# ATtiny85.net
KiCad netlist of a schematic drawn in EAGLE
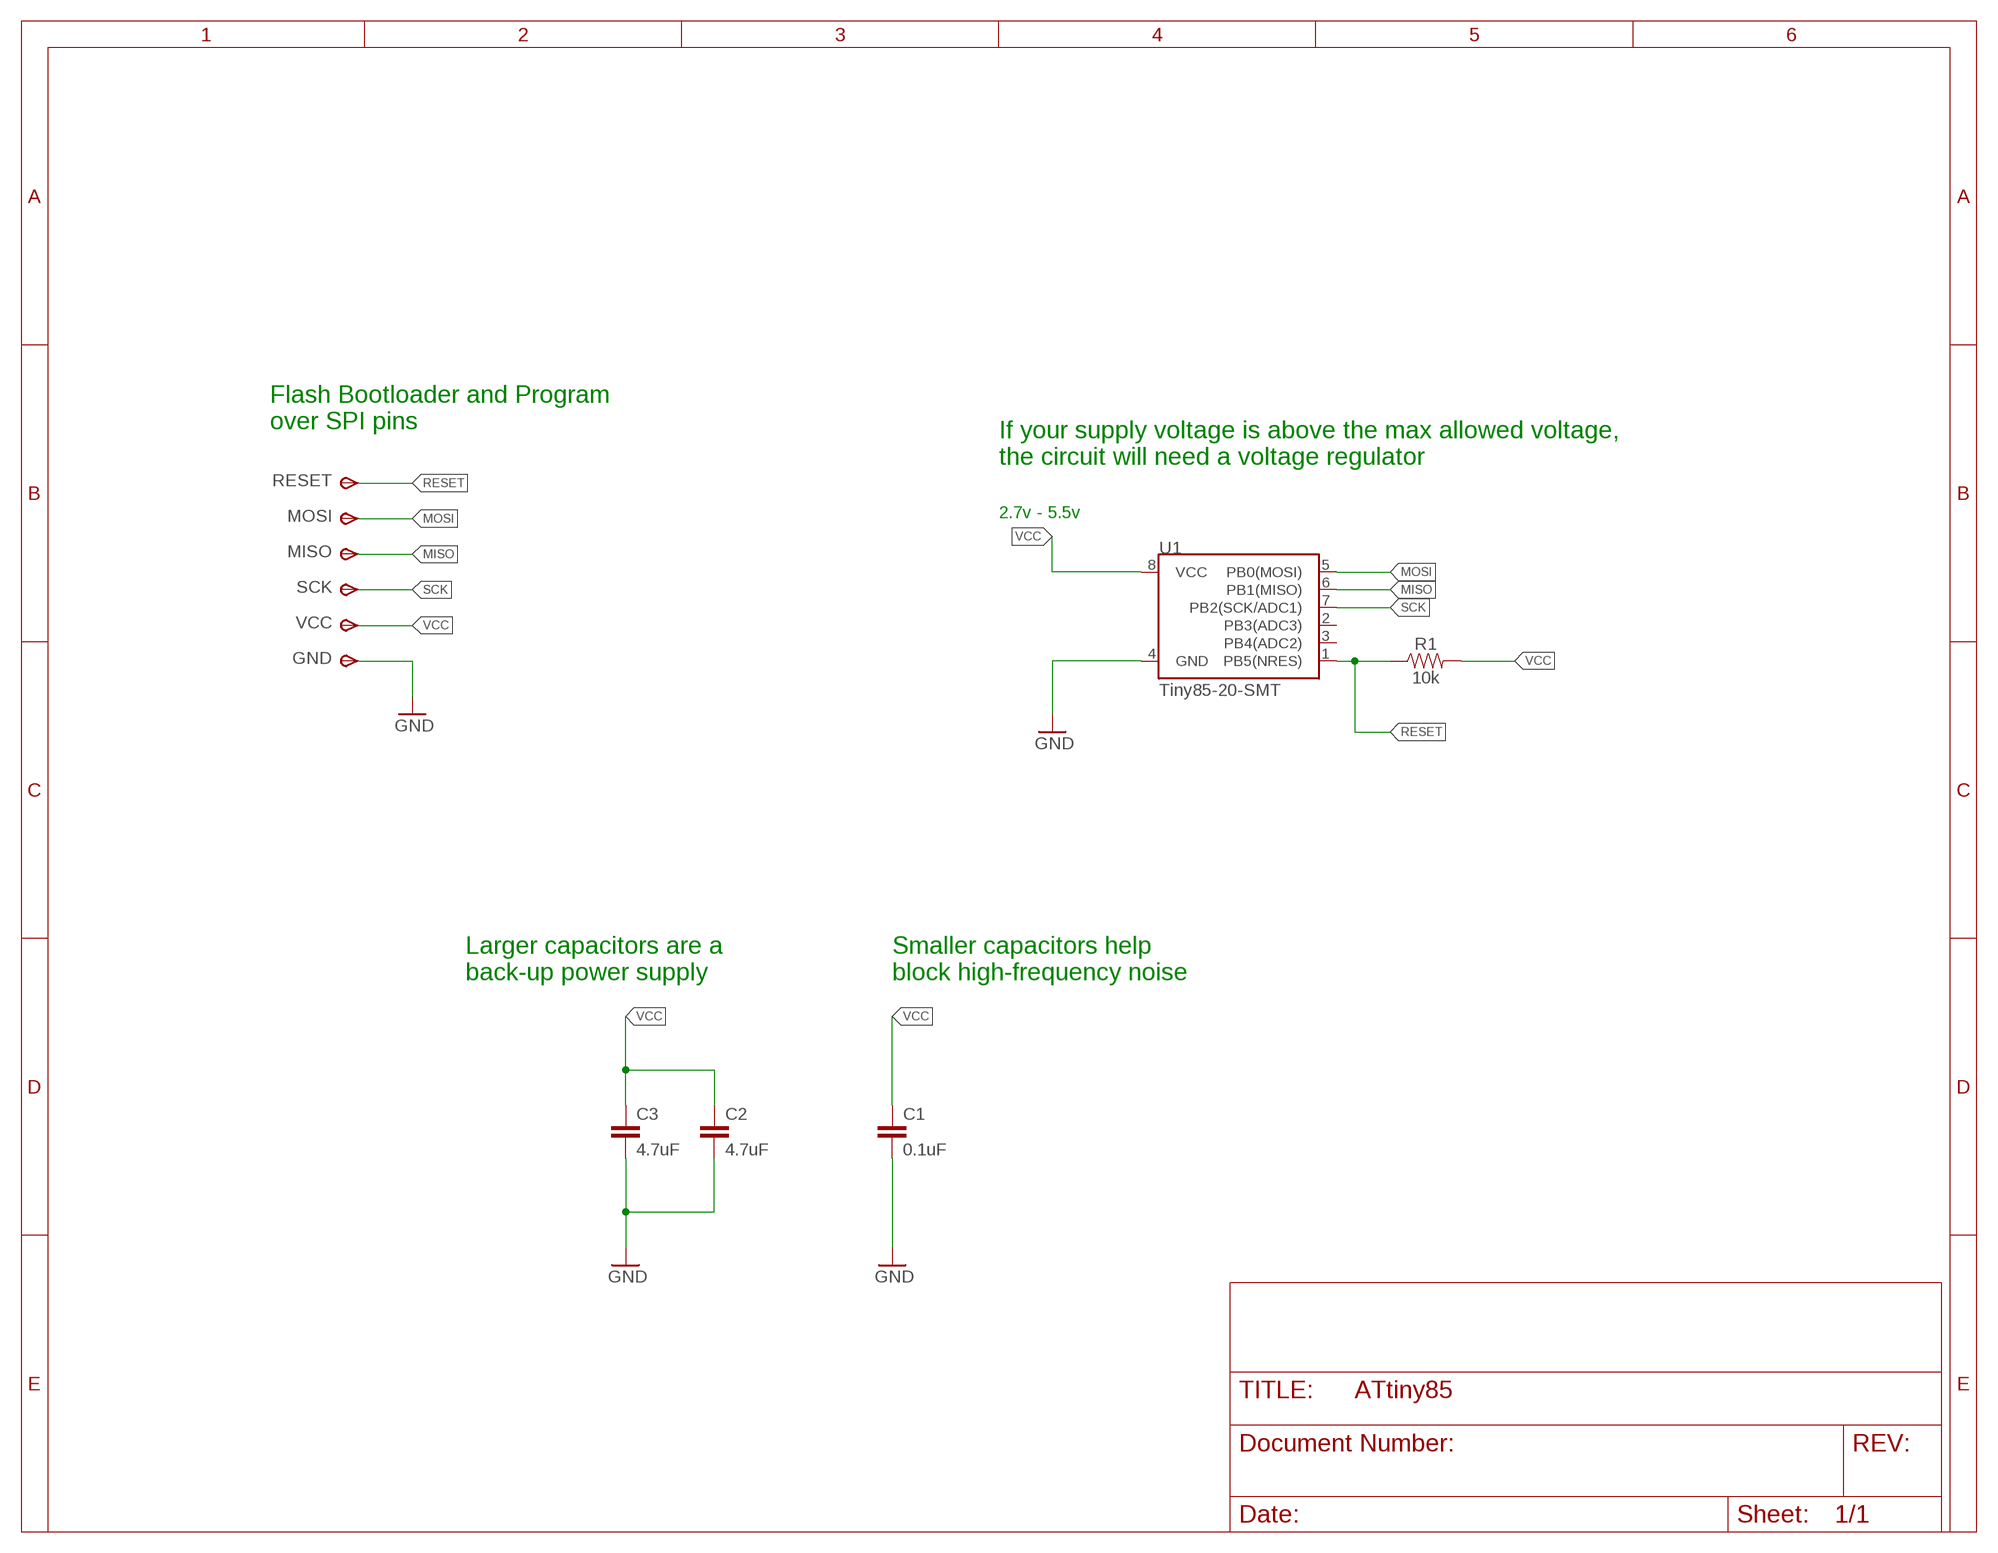
[diagram p0: schematic, sheet 1]

(export (version "E")
  (design (tool "Eeschema 10.0.6"))
  (components
    (comp (ref "C1")
      (value "0.1uF")
      (footprint "eagle-import:0603")
      (libsource (lib "eagle-import") (part "0.1UF-0603-25V-5%"))
    )
    (comp (ref "C2")
      (value "4.7uF")
      (footprint "eagle-import:0603")
      (libsource (lib "eagle-import") (part "4.7UF0603"))
    )
    (comp (ref "C3")
      (value "4.7uF")
      (footprint "eagle-import:0603")
      (libsource (lib "eagle-import") (part "4.7UF0603"))
    )
    (comp (ref "GND")
      (value "TPSTP14SQ")
      (footprint "eagle-import:TP14SQ")
      (libsource (lib "eagle-import") (part "TPSTP14SQ"))
    )
    (comp (ref "MISO")
      (value "TPSTP14SQ")
      (footprint "eagle-import:TP14SQ")
      (libsource (lib "eagle-import") (part "TPSTP14SQ"))
    )
    (comp (ref "MOSI")
      (value "TPSTP14SQ")
      (footprint "eagle-import:TP14SQ")
      (libsource (lib "eagle-import") (part "TPSTP14SQ"))
    )
    (comp (ref "R1")
      (value "10k")
      (footprint "eagle-import:0603")
      (libsource (lib "eagle-import") (part "10KOHM-0603-1/10W-1%"))
    )
    (comp (ref "RESET")
      (value "TPSTP14SQ")
      (footprint "eagle-import:TP14SQ")
      (libsource (lib "eagle-import") (part "TPSTP14SQ"))
    )
    (comp (ref "SCK")
      (value "TPSTP14SQ")
      (footprint "eagle-import:TP14SQ")
      (libsource (lib "eagle-import") (part "TPSTP14SQ"))
    )
    (comp (ref "U1")
      (value "Tiny85-20-SMT")
      (footprint "eagle-import:SO08-EIAJ_MCU")
      (libsource (lib "eagle-import") (part "ATTINY45TINY85-20-SMT"))
    )
    (comp (ref "VCC")
      (value "TPSTP14SQ")
      (footprint "eagle-import:TP14SQ")
      (libsource (lib "eagle-import") (part "TPSTP14SQ"))
    )
  )
  (nets
    (net (code "1") (name "GND") (class "Default")
      (node (ref "C1") (pin "2") (pinfunction "2_2") (pintype "passive"))
      (node (ref "C2") (pin "2") (pinfunction "2_2") (pintype "passive"))
      (node (ref "C3") (pin "2") (pinfunction "2_2") (pintype "passive"))
      (node (ref "GND") (pin "TP") (pinfunction "PP_TP") (pintype "input"))
      (node (ref "U1") (pin "4") (pinfunction "GND_4") (pintype "bidirectional"))
    )
    (net (code "2") (name "MISO") (class "Default")
      (node (ref "MISO") (pin "TP") (pinfunction "PP_TP") (pintype "input"))
      (node (ref "U1") (pin "6") (pinfunction "PB1(MISO)_6") (pintype "bidirectional"))
    )
    (net (code "3") (name "MOSI") (class "Default")
      (node (ref "MOSI") (pin "TP") (pinfunction "PP_TP") (pintype "input"))
      (node (ref "U1") (pin "5") (pinfunction "PB0(MOSI)_5") (pintype "bidirectional"))
    )
    (net (code "4") (name "RESET") (class "Default")
      (node (ref "R1") (pin "1") (pinfunction "1_1") (pintype "passive"))
      (node (ref "RESET") (pin "TP") (pinfunction "PP_TP") (pintype "input"))
      (node (ref "U1") (pin "1") (pinfunction "PB5(NRES)_1") (pintype "bidirectional"))
    )
    (net (code "5") (name "SCK") (class "Default")
      (node (ref "SCK") (pin "TP") (pinfunction "PP_TP") (pintype "input"))
      (node (ref "U1") (pin "7") (pinfunction "PB2(SCK/ADC1)_7") (pintype "bidirectional"))
    )
    (net (code "6") (name "VCC") (class "Default")
      (node (ref "C1") (pin "1") (pinfunction "1_1") (pintype "passive"))
      (node (ref "C2") (pin "1") (pinfunction "1_1") (pintype "passive"))
      (node (ref "C3") (pin "1") (pinfunction "1_1") (pintype "passive"))
      (node (ref "R1") (pin "2") (pinfunction "2_2") (pintype "passive"))
      (node (ref "U1") (pin "8") (pinfunction "VCC_8") (pintype "bidirectional"))
      (node (ref "VCC") (pin "TP") (pinfunction "PP_TP") (pintype "input"))
    )
    (net (code "7") (name "unconnected-(U1-PB3(ADC3)-Pad2)") (class "Default")
      (node (ref "U1") (pin "2") (pinfunction "PB3(ADC3)_2") (pintype "bidirectional"))
    )
    (net (code "8") (name "unconnected-(U1-PB4(ADC2)-Pad3)") (class "Default")
      (node (ref "U1") (pin "3") (pinfunction "PB4(ADC2)_3") (pintype "bidirectional"))
    )
  )
)
